# Abhishek-schematic.net
KiCad netlist of a schematic drawn in EAGLE
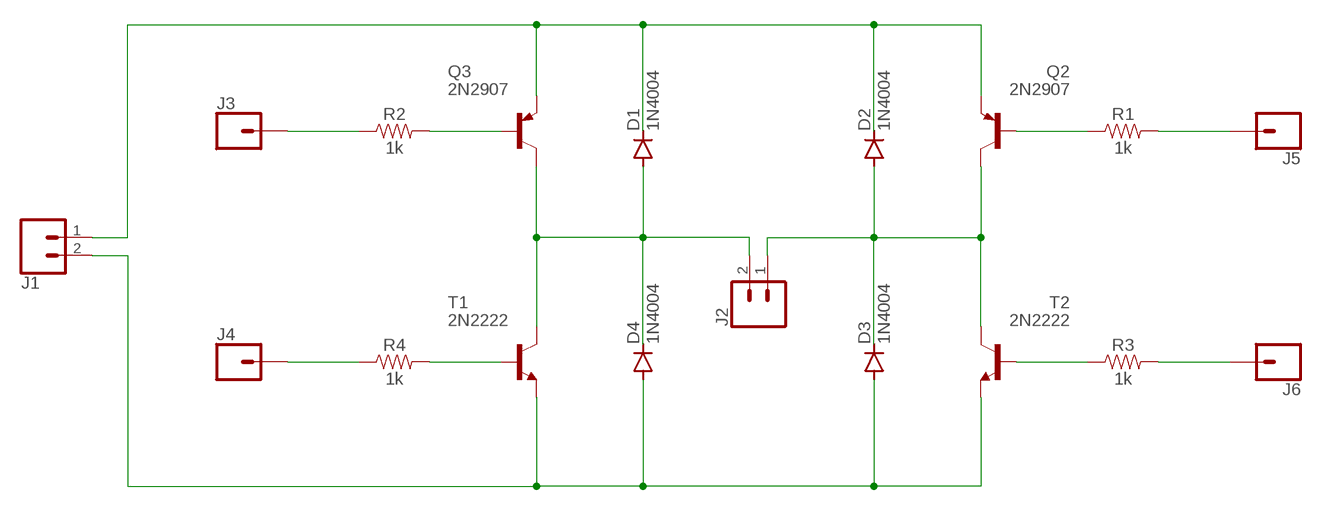
[diagram p0: schematic, sheet 1]

(export (version "E")
  (design (tool "Eeschema 10.0.6"))
  (components
    (comp (ref "D1")
      (value "1N4004")
      (footprint "eagle-import:DO41-10")
      (libsource (lib "eagle-import") (part "1N4004"))
    )
    (comp (ref "D2")
      (value "1N4004")
      (footprint "eagle-import:DO41-10")
      (libsource (lib "eagle-import") (part "1N4004"))
    )
    (comp (ref "D3")
      (value "1N4004")
      (footprint "eagle-import:DO41-10")
      (libsource (lib "eagle-import") (part "1N4004"))
    )
    (comp (ref "D4")
      (value "1N4004")
      (footprint "eagle-import:DO41-10")
      (libsource (lib "eagle-import") (part "1N4004"))
    )
    (comp (ref "J1")
      (value "CONN_02")
      (footprint "eagle-import:1X02")
      (libsource (lib "eagle-import") (part "CONN_02"))
    )
    (comp (ref "J2")
      (value "CONN_02")
      (footprint "eagle-import:1X02")
      (libsource (lib "eagle-import") (part "CONN_02"))
    )
    (comp (ref "J3")
      (value "CONN_01")
      (footprint "eagle-import:1X01")
      (libsource (lib "eagle-import") (part "CONN_01"))
    )
    (comp (ref "J4")
      (value "CONN_01")
      (footprint "eagle-import:1X01")
      (libsource (lib "eagle-import") (part "CONN_01"))
    )
    (comp (ref "J5")
      (value "CONN_01")
      (footprint "eagle-import:1X01")
      (libsource (lib "eagle-import") (part "CONN_01"))
    )
    (comp (ref "J6")
      (value "CONN_01")
      (footprint "eagle-import:1X01")
      (libsource (lib "eagle-import") (part "CONN_01"))
    )
    (comp (ref "Q2")
      (value "2N2907")
      (footprint "eagle-import:TO18")
      (libsource (lib "eagle-import") (part "2N2907"))
    )
    (comp (ref "Q3")
      (value "2N2907")
      (footprint "eagle-import:TO18")
      (libsource (lib "eagle-import") (part "2N2907"))
    )
    (comp (ref "R1")
      (value "1k")
      (footprint "eagle-import:AXIAL-0.3")
      (libsource (lib "eagle-import") (part "1KOHM-HORIZ-1/4W-1%"))
    )
    (comp (ref "R2")
      (value "1k")
      (footprint "eagle-import:AXIAL-0.3")
      (libsource (lib "eagle-import") (part "1KOHM-HORIZ-1/4W-1%"))
    )
    (comp (ref "R3")
      (value "1k")
      (footprint "eagle-import:AXIAL-0.3")
      (libsource (lib "eagle-import") (part "1KOHM-HORIZ-1/4W-1%"))
    )
    (comp (ref "R4")
      (value "1k")
      (footprint "eagle-import:AXIAL-0.3")
      (libsource (lib "eagle-import") (part "1KOHM-HORIZ-1/4W-1%"))
    )
    (comp (ref "T1")
      (value "2N2222")
      (footprint "eagle-import:TO18")
      (libsource (lib "eagle-import") (part "2N2222"))
    )
    (comp (ref "T2")
      (value "2N2222")
      (footprint "eagle-import:TO18")
      (libsource (lib "eagle-import") (part "2N2222"))
    )
  )
  (nets
    (net (code "1") (name "Net-(Q2-B)") (class "Default")
      (node (ref "Q2") (pin "2") (pinfunction "B_2") (pintype "passive"))
      (node (ref "R1") (pin "P$1") (pinfunction "1_P$1") (pintype "passive"))
    )
    (net (code "2") (name "Net-(Q2-C)") (class "Default")
      (node (ref "D2") (pin "A") (pinfunction "A_A") (pintype "passive"))
      (node (ref "D3") (pin "C") (pinfunction "C_C") (pintype "passive"))
      (node (ref "J2") (pin "1") (pinfunction "1_1") (pintype "passive"))
      (node (ref "Q2") (pin "3") (pinfunction "C_3") (pintype "passive"))
      (node (ref "T2") (pin "3") (pinfunction "C_3") (pintype "passive"))
    )
    (net (code "3") (name "Net-(Q2-E)") (class "Default")
      (node (ref "D1") (pin "C") (pinfunction "C_C") (pintype "passive"))
      (node (ref "D2") (pin "C") (pinfunction "C_C") (pintype "passive"))
      (node (ref "J1") (pin "1") (pinfunction "1_1") (pintype "passive"))
      (node (ref "Q2") (pin "1") (pinfunction "E_1") (pintype "passive"))
      (node (ref "Q3") (pin "1") (pinfunction "E_1") (pintype "passive"))
    )
    (net (code "4") (name "Net-(Q3-B)") (class "Default")
      (node (ref "Q3") (pin "2") (pinfunction "B_2") (pintype "passive"))
      (node (ref "R2") (pin "P$2") (pinfunction "2_P$2") (pintype "passive"))
    )
    (net (code "5") (name "Net-(Q3-C)") (class "Default")
      (node (ref "D1") (pin "A") (pinfunction "A_A") (pintype "passive"))
      (node (ref "D4") (pin "C") (pinfunction "C_C") (pintype "passive"))
      (node (ref "J2") (pin "2") (pinfunction "2_2") (pintype "passive"))
      (node (ref "Q3") (pin "3") (pinfunction "C_3") (pintype "passive"))
      (node (ref "T1") (pin "3") (pinfunction "C_3") (pintype "passive"))
    )
    (net (code "6") (name "Net-(R1-2)") (class "Default")
      (node (ref "J5") (pin "1") (pinfunction "1_1") (pintype "passive"))
      (node (ref "R1") (pin "P$2") (pinfunction "2_P$2") (pintype "passive"))
    )
    (net (code "7") (name "Net-(R2-1)") (class "Default")
      (node (ref "J3") (pin "1") (pinfunction "1_1") (pintype "passive"))
      (node (ref "R2") (pin "P$1") (pinfunction "1_P$1") (pintype "passive"))
    )
    (net (code "8") (name "Net-(R3-1)") (class "Default")
      (node (ref "R3") (pin "P$1") (pinfunction "1_P$1") (pintype "passive"))
      (node (ref "T2") (pin "2") (pinfunction "B_2") (pintype "passive"))
    )
    (net (code "9") (name "Net-(R3-2)") (class "Default")
      (node (ref "J6") (pin "1") (pinfunction "1_1") (pintype "passive"))
      (node (ref "R3") (pin "P$2") (pinfunction "2_P$2") (pintype "passive"))
    )
    (net (code "10") (name "Net-(R4-1)") (class "Default")
      (node (ref "J4") (pin "1") (pinfunction "1_1") (pintype "passive"))
      (node (ref "R4") (pin "P$1") (pinfunction "1_P$1") (pintype "passive"))
    )
    (net (code "11") (name "Net-(R4-2)") (class "Default")
      (node (ref "R4") (pin "P$2") (pinfunction "2_P$2") (pintype "passive"))
      (node (ref "T1") (pin "2") (pinfunction "B_2") (pintype "passive"))
    )
    (net (code "12") (name "Net-(T1-E)") (class "Default")
      (node (ref "D3") (pin "A") (pinfunction "A_A") (pintype "passive"))
      (node (ref "D4") (pin "A") (pinfunction "A_A") (pintype "passive"))
      (node (ref "J1") (pin "2") (pinfunction "2_2") (pintype "passive"))
      (node (ref "T1") (pin "1") (pinfunction "E_1") (pintype "passive"))
      (node (ref "T2") (pin "1") (pinfunction "E_1") (pintype "passive"))
    )
  )
)
